# USB_Audio_DAC.net
KiCad netlist of a schematic drawn in Altium Designer
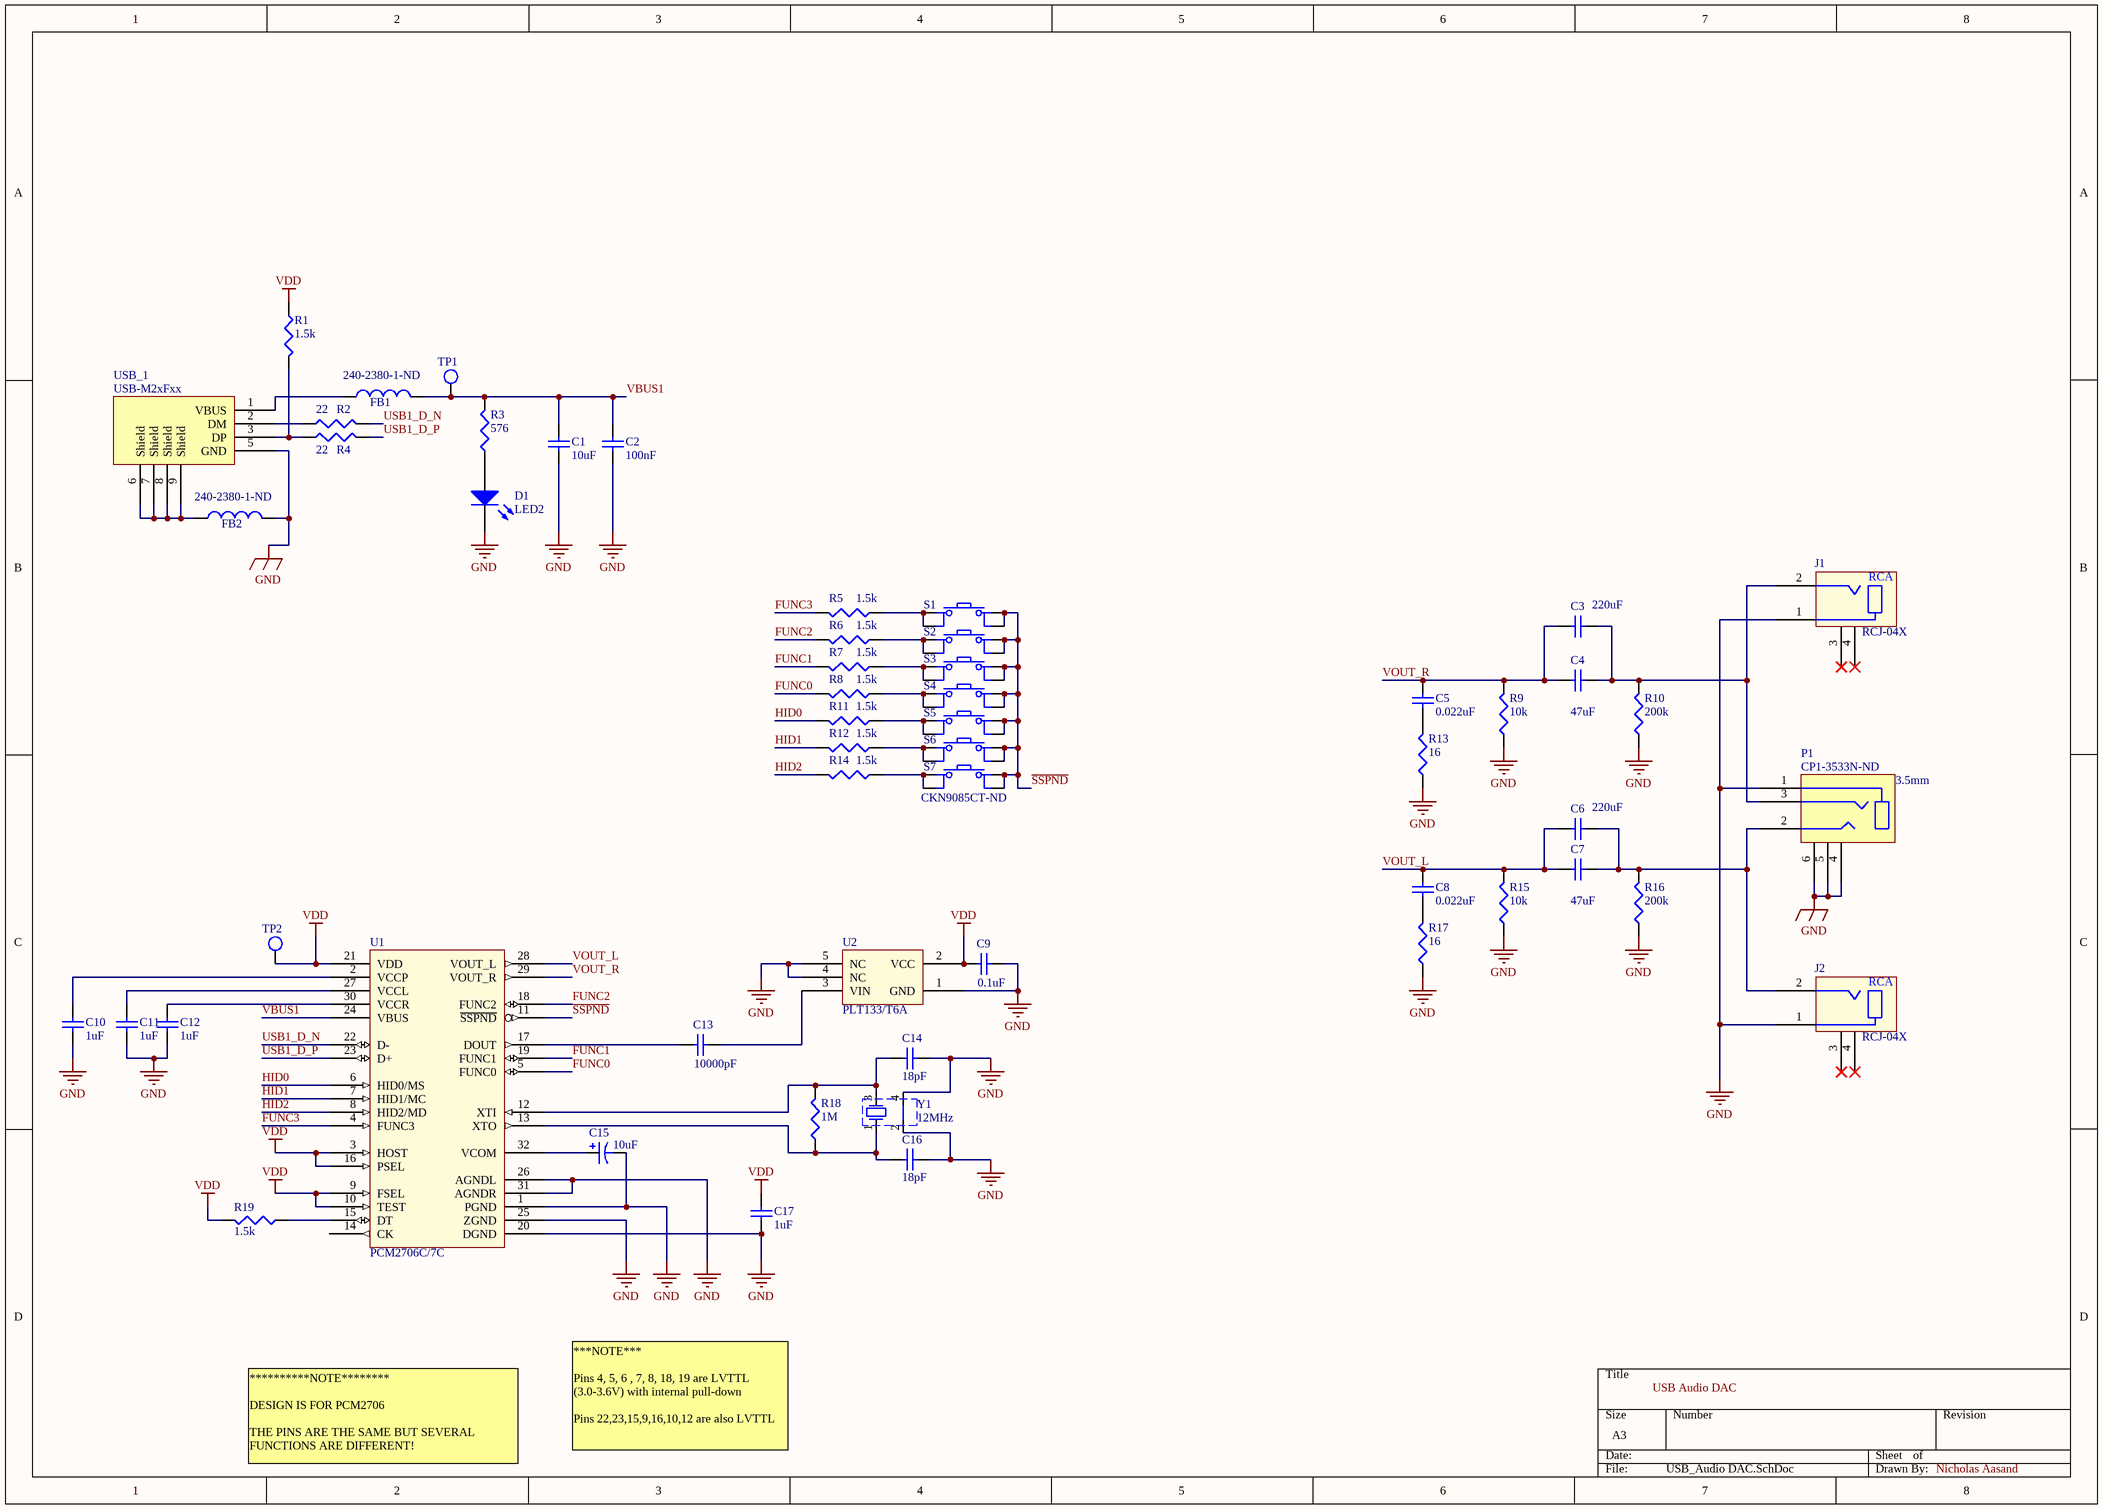
[diagram p0: USB_Audio DAC.SchDoc]

(export (version "E")
  (design (tool "Eeschema 10.0.6"))
  (components
    (comp (ref "C1")
      (value "10uF")
      (footprint "C0805")
      (description "Capacitor (Semiconductor SIM Model)")
      (fields (field (name "Comment") "0805") (field (name "PUBLISHER") "Altium Limited"))
      (libsource (lib "Miscellaneous Devices") (part "Cap Semi"))
    )
    (comp (ref "C2")
      (value "100nF")
      (footprint "C0805")
      (description "Capacitor (Semiconductor SIM Model)")
      (fields (field (name "Comment") "0805") (field (name "PUBLISHER") "Altium Limited"))
      (libsource (lib "Miscellaneous Devices") (part "Cap Semi"))
    )
    (comp (ref "C3")
      (value "220uF")
      (footprint "CAPPR5-10x12.5")
      (description "Capacitor")
      (fields (field (name "Comment") "Cap") (field (name "PUBLISHER") "Altium Limited"))
      (libsource (lib "Miscellaneous Devices") (part "Cap"))
    )
    (comp (ref "C4")
      (value "47uF")
      (footprint "CAPPR2-5x11")
      (description "Capacitor")
      (fields (field (name "Comment") "Cap") (field (name "PUBLISHER") "Altium Limited"))
      (libsource (lib "Miscellaneous Devices") (part "Cap"))
    )
    (comp (ref "C5")
      (value "0.022uF")
      (footprint "C0805")
      (description "Capacitor (Semiconductor SIM Model)")
      (fields (field (name "Comment") "0805") (field (name "PUBLISHER") "Altium Limited"))
      (libsource (lib "Miscellaneous Devices") (part "Cap Semi"))
    )
    (comp (ref "C6")
      (value "220uF")
      (footprint "CAPPR5-10x12.5")
      (description "Capacitor")
      (fields (field (name "Comment") "Cap") (field (name "PUBLISHER") "Altium Limited"))
      (libsource (lib "Miscellaneous Devices") (part "Cap"))
    )
    (comp (ref "C7")
      (value "47uF")
      (footprint "CAPPR2-5x11")
      (description "Capacitor")
      (fields (field (name "Comment") "Cap") (field (name "PUBLISHER") "Altium Limited"))
      (libsource (lib "Miscellaneous Devices") (part "Cap"))
    )
    (comp (ref "C8")
      (value "0.022uF")
      (footprint "C0805")
      (description "Capacitor (Semiconductor SIM Model)")
      (fields (field (name "Comment") "0805") (field (name "PUBLISHER") "Altium Limited"))
      (libsource (lib "Miscellaneous Devices") (part "Cap Semi"))
    )
    (comp (ref "C9")
      (value "0.1uF")
      (footprint "C0805")
      (description "Capacitor (Semiconductor SIM Model)")
      (fields (field (name "Comment") "Cap Semi") (field (name "PUBLISHER") "Altium Limited"))
      (libsource (lib "Miscellaneous Devices") (part "Cap Semi"))
    )
    (comp (ref "C10")
      (value "1uF")
      (footprint "C0805")
      (description "Capacitor (Semiconductor SIM Model)")
      (fields (field (name "Comment") "0805") (field (name "PUBLISHER") "Altium Limited"))
      (libsource (lib "Miscellaneous Devices") (part "Cap Semi"))
    )
    (comp (ref "C11")
      (value "1uF")
      (footprint "C0805")
      (description "Capacitor (Semiconductor SIM Model)")
      (fields (field (name "Comment") "0805") (field (name "PUBLISHER") "Altium Limited"))
      (libsource (lib "Miscellaneous Devices") (part "Cap Semi"))
    )
    (comp (ref "C12")
      (value "1uF")
      (footprint "C0805")
      (description "Capacitor (Semiconductor SIM Model)")
      (fields (field (name "Comment") "0805") (field (name "PUBLISHER") "Altium Limited"))
      (libsource (lib "Miscellaneous Devices") (part "Cap Semi"))
    )
    (comp (ref "C13")
      (value "10000pF")
      (footprint "C0805")
      (description "Capacitor (Semiconductor SIM Model)")
      (fields (field (name "Comment") "Cap Semi") (field (name "PUBLISHER") "Altium Limited"))
      (libsource (lib "Miscellaneous Devices") (part "Cap Semi"))
    )
    (comp (ref "C14")
      (value "18pF")
      (footprint "CAPC1608L")
      (description "Capacitor (Semiconductor SIM Model)")
      (fields (field (name "Comment") "0805") (field (name "PUBLISHER") "Altium Limited"))
      (libsource (lib "Miscellaneous Devices") (part "Cap Semi"))
    )
    (comp (ref "C15")
      (value "10uF")
      (footprint "Cap_ALUM_SMD")
      (description "Polarized Capacitor (Surface Mount)")
      (fields (field (name "Comment") "Cap Pol3") (field (name "PUBLISHER") "Altium Limited"))
      (libsource (lib "Miscellaneous Devices") (part "Cap Pol3"))
    )
    (comp (ref "C16")
      (value "18pF")
      (footprint "CAPC1608L")
      (description "Capacitor (Semiconductor SIM Model)")
      (fields (field (name "Comment") "0805") (field (name "PUBLISHER") "Altium Limited"))
      (libsource (lib "Miscellaneous Devices") (part "Cap Semi"))
    )
    (comp (ref "C17")
      (value "1uF")
      (footprint "C0805")
      (description "Capacitor (Semiconductor SIM Model)")
      (fields (field (name "Comment") "0805") (field (name "PUBLISHER") "Altium Limited"))
      (libsource (lib "Miscellaneous Devices") (part "Cap Semi"))
    )
    (comp (ref "D1")
      (value "LED2")
      (footprint "2.00mm L x 1.25mm W")
      (description "Typical RED, GREEN, YELLOW, AMBER GaAs LED")
      (fields (field (name "PUBLISHER") "Altium Limited"))
      (libsource (lib "Miscellaneous Devices") (part "LED2"))
    )
    (comp (ref "FB1")
      (value "0603")
      (footprint "INDC1608L")
      (description "Inductor")
      (fields (field (name "DIGIKEY") "240-2380-1-ND") (field (name "PUBLISHER") "Altium Limited"))
      (libsource (lib "Miscellaneous Devices") (part "Inductor"))
    )
    (comp (ref "FB2")
      (value "0603")
      (footprint "INDC1608L")
      (description "Inductor")
      (fields (field (name "DIGIKEY") "240-2380-1-ND") (field (name "PUBLISHER") "Altium Limited"))
      (libsource (lib "Miscellaneous Devices") (part "Inductor"))
    )
    (comp (ref "J1")
      (value "RCJ-04X")
      (footprint "RCJ-04X")
      (description "RCJ-04X series RCA connector")
      (libsource (lib "RCA_Audio_Jack") (part "RCJ-04X"))
    )
    (comp (ref "J2")
      (value "RCJ-04X")
      (footprint "RCJ-04X")
      (description "RCJ-04X series RCA connector")
      (libsource (lib "RCA_Audio_Jack") (part "RCJ-04X"))
    )
    (comp (ref "P1")
      (value "SJ1-3533NS")
      (footprint "SJ1-3533NS")
      (description "CUI 3.5mm Audio Jack Shielded")
      (fields (field (name "DIGIKEY") "CP1-3533N-ND"))
      (libsource (lib "Audio_Jacks") (part "SJ1-3533NS"))
    )
    (comp (ref "R1")
      (value "1.5k")
      (footprint "RESC2012L")
      (description "Resistor")
      (fields (field (name "Comment") "0805"))
      (libsource (lib "Miscellaneous Devices") (part "Res3"))
    )
    (comp (ref "R2")
      (value "22")
      (footprint "6-0805_N")
      (description "Resistor")
      (fields (field (name "Comment") "Res3") (field (name "PUBLISHER") "Altium Limited"))
      (libsource (lib "Miscellaneous Devices") (part "Res3"))
    )
    (comp (ref "R3")
      (value "576")
      (footprint "6-0805_N")
      (description "Resistor")
      (fields (field (name "Comment") "Res3") (field (name "PUBLISHER") "Altium Limited"))
      (libsource (lib "Miscellaneous Devices") (part "Res3"))
    )
    (comp (ref "R4")
      (value "22")
      (footprint "6-0805_N")
      (description "Resistor")
      (fields (field (name "Comment") "Res3") (field (name "PUBLISHER") "Altium Limited"))
      (libsource (lib "Miscellaneous Devices") (part "Res3"))
    )
    (comp (ref "R5")
      (value "1.5k")
      (footprint "RESC2012L")
      (description "Resistor")
      (fields (field (name "Comment") "0805"))
      (libsource (lib "Miscellaneous Devices") (part "Res3"))
    )
    (comp (ref "R6")
      (value "1.5k")
      (footprint "RESC2012L")
      (description "Resistor")
      (fields (field (name "Comment") "0805"))
      (libsource (lib "Miscellaneous Devices") (part "Res3"))
    )
    (comp (ref "R7")
      (value "1.5k")
      (footprint "RESC2012L")
      (description "Resistor")
      (fields (field (name "Comment") "0805"))
      (libsource (lib "Miscellaneous Devices") (part "Res3"))
    )
    (comp (ref "R8")
      (value "1.5k")
      (footprint "RESC2012L")
      (description "Resistor")
      (fields (field (name "Comment") "0805"))
      (libsource (lib "Miscellaneous Devices") (part "Res3"))
    )
    (comp (ref "R9")
      (value "10k")
      (footprint "RESC2012L")
      (description "Resistor")
      (fields (field (name "Comment") "0805"))
      (libsource (lib "Miscellaneous Devices") (part "Res3"))
    )
    (comp (ref "R10")
      (value "200k")
      (footprint "RESC2012L")
      (description "Resistor")
      (fields (field (name "Comment") "0805"))
      (libsource (lib "Miscellaneous Devices") (part "Res3"))
    )
    (comp (ref "R11")
      (value "1.5k")
      (footprint "RESC2012L")
      (description "Resistor")
      (fields (field (name "Comment") "0805"))
      (libsource (lib "Miscellaneous Devices") (part "Res3"))
    )
    (comp (ref "R12")
      (value "1.5k")
      (footprint "RESC2012L")
      (description "Resistor")
      (fields (field (name "Comment") "0805"))
      (libsource (lib "Miscellaneous Devices") (part "Res3"))
    )
    (comp (ref "R13")
      (value "16")
      (footprint "6-0805_N")
      (description "Resistor")
      (fields (field (name "Comment") "Res3") (field (name "PUBLISHER") "Altium Limited"))
      (libsource (lib "Miscellaneous Devices") (part "Res3"))
    )
    (comp (ref "R14")
      (value "1.5k")
      (footprint "RESC2012L")
      (description "Resistor")
      (fields (field (name "Comment") "0805"))
      (libsource (lib "Miscellaneous Devices") (part "Res3"))
    )
    (comp (ref "R15")
      (value "10k")
      (footprint "RESC2012L")
      (description "Resistor")
      (fields (field (name "Comment") "0805"))
      (libsource (lib "Miscellaneous Devices") (part "Res3"))
    )
    (comp (ref "R16")
      (value "200k")
      (footprint "RESC2012L")
      (description "Resistor")
      (fields (field (name "Comment") "0805"))
      (libsource (lib "Miscellaneous Devices") (part "Res3"))
    )
    (comp (ref "R17")
      (value "16")
      (footprint "6-0805_N")
      (description "Resistor")
      (fields (field (name "Comment") "Res3") (field (name "PUBLISHER") "Altium Limited"))
      (libsource (lib "Miscellaneous Devices") (part "Res3"))
    )
    (comp (ref "R18")
      (value "1M")
      (footprint "6-0805_N")
      (description "Resistor")
      (fields (field (name "Comment") "Res3") (field (name "PUBLISHER") "Altium Limited"))
      (libsource (lib "Miscellaneous Devices") (part "Res3"))
    )
    (comp (ref "R19")
      (value "1.5k")
      (footprint "RESC2012L")
      (description "Resistor")
      (fields (field (name "Comment") "0805"))
      (libsource (lib "Miscellaneous Devices") (part "Res3"))
    )
    (comp (ref "S1")
      (value "SW")
      (footprint "C&K_PTS645_SMD")
      (description "SPST Tactile switch - generic")
      (libsource (lib "Switches") (part "SPST-4"))
    )
    (comp (ref "S2")
      (value "SW")
      (footprint "C&K_PTS645_SMD")
      (description "SPST Tactile switch - generic")
      (libsource (lib "Switches") (part "SPST-4"))
    )
    (comp (ref "S3")
      (value "SW")
      (footprint "C&K_PTS645_SMD")
      (description "SPST Tactile switch - generic")
      (libsource (lib "Switches") (part "SPST-4"))
    )
    (comp (ref "S4")
      (value "SW")
      (footprint "C&K_PTS645_SMD")
      (description "SPST Tactile switch - generic")
      (libsource (lib "Switches") (part "SPST-4"))
    )
    (comp (ref "S5")
      (value "SW")
      (footprint "C&K_PTS645_SMD")
      (description "SPST Tactile switch - generic")
      (libsource (lib "Switches") (part "SPST-4"))
    )
    (comp (ref "S6")
      (value "SW")
      (footprint "C&K_PTS645_SMD")
      (description "SPST Tactile switch - generic")
      (libsource (lib "Switches") (part "SPST-4"))
    )
    (comp (ref "S7")
      (value "SW")
      (footprint "C&K_PTS645_SMD")
      (description "SPST Tactile switch - generic")
      (fields (field (name "DIGIKEY") "CKN9085CT-ND"))
      (libsource (lib "Switches") (part "SPST-4"))
    )
    (comp (ref "TP1")
      (value "Test point")
      (footprint "Test_Pad")
      (description "Test point pad")
      (libsource (lib "Connectors") (part "Test_Pad"))
    )
    (comp (ref "TP2")
      (value "Test point")
      (footprint "Test_Pad")
      (description "Test point pad")
      (libsource (lib "Connectors") (part "Test_Pad"))
    )
    (comp (ref "U1")
      (value "PCM2706C/7C")
      (footprint "TQFP80P970X970X120-32N")
      (description "Stereo Audio DAC with USB Interface, Single-Ended Headphone Out, S/PDIF Output")
      (libsource (lib "PCM2707") (part "PCM2707"))
    )
    (comp (ref "U2")
      (value "PLT133/T6A")
      (footprint "PLT133/T10W")
      (description "TRANSMITTER FBR OPT IR PHOTOLINK 660nm")
      (libsource (lib "PLT133_T6A") (part "PLT133/T6A"))
    )
    (comp (ref "USB_1")
      (value "USB-M2xFxx")
      (footprint "USB-M2xFxx")
      (description "USB Mini-B for USB-M2xFxx")
      (libsource (lib "USB-M2xFxx") (part "USB-M2xFxx"))
    )
    (comp (ref "Y1")
      (value "12MHz")
      (footprint "TXC-7M")
      (description "Crystal Oscillator - 4 Pin")
      (libsource (lib "XTALS") (part "XTAL-4"))
    )
  )
  (nets
    (net (code "1") (name "/FUNC0") (class "Default")
      (node (ref "R8") (pin "2") (pinfunction "2_2") (pintype "passive"))
      (node (ref "U1") (pin "5") (pinfunction "FUNC0_5") (pintype "bidirectional"))
    )
    (net (code "2") (name "/FUNC1") (class "Default")
      (node (ref "R7") (pin "2") (pinfunction "2_2") (pintype "passive"))
      (node (ref "U1") (pin "19") (pinfunction "FUNC1_19") (pintype "bidirectional"))
    )
    (net (code "3") (name "/FUNC2") (class "Default")
      (node (ref "R6") (pin "2") (pinfunction "2_2") (pintype "passive"))
      (node (ref "U1") (pin "18") (pinfunction "FUNC2_18") (pintype "bidirectional"))
    )
    (net (code "4") (name "/FUNC3") (class "Default")
      (node (ref "R5") (pin "2") (pinfunction "2_2") (pintype "passive"))
      (node (ref "U1") (pin "4") (pinfunction "FUNC3_4") (pintype "input"))
    )
    (net (code "5") (name "/HID0") (class "Default")
      (node (ref "R11") (pin "2") (pinfunction "2_2") (pintype "passive"))
      (node (ref "U1") (pin "6") (pinfunction "HID0/MS_6") (pintype "input"))
    )
    (net (code "6") (name "/HID1") (class "Default")
      (node (ref "R12") (pin "2") (pinfunction "2_2") (pintype "passive"))
      (node (ref "U1") (pin "7") (pinfunction "HID1/MC_7") (pintype "input"))
    )
    (net (code "7") (name "/HID2") (class "Default")
      (node (ref "R14") (pin "2") (pinfunction "2_2") (pintype "passive"))
      (node (ref "U1") (pin "8") (pinfunction "HID2/MD_8") (pintype "input"))
    )
    (net (code "8") (name "/USB1_D_N") (class "Default")
      (node (ref "R2") (pin "2") (pinfunction "2_2") (pintype "passive"))
      (node (ref "U1") (pin "22") (pinfunction "D-_22") (pintype "bidirectional"))
    )
    (net (code "9") (name "/USB1_D_P") (class "Default")
      (node (ref "R4") (pin "2") (pinfunction "2_2") (pintype "passive"))
      (node (ref "U1") (pin "23") (pinfunction "D+_23") (pintype "bidirectional"))
    )
    (net (code "10") (name "/VBUS1") (class "Default")
      (node (ref "C1") (pin "1") (pinfunction "1_1") (pintype "passive"))
      (node (ref "C2") (pin "1") (pinfunction "1_1") (pintype "passive"))
      (node (ref "FB1") (pin "2") (pinfunction "2_2") (pintype "passive"))
      (node (ref "R3") (pin "2") (pinfunction "2_2") (pintype "passive"))
      (node (ref "TP1") (pin "1") (pinfunction "1_1") (pintype "passive"))
      (node (ref "U1") (pin "24") (pinfunction "VBUS_24") (pintype "power_in"))
    )
    (net (code "11") (name "/VOUT_L") (class "Default")
      (node (ref "C6") (pin "1") (pinfunction "1_1") (pintype "passive"))
      (node (ref "C7") (pin "1") (pinfunction "1_1") (pintype "passive"))
      (node (ref "C8") (pin "1") (pinfunction "1_1") (pintype "passive"))
      (node (ref "R15") (pin "2") (pinfunction "2_2") (pintype "passive"))
      (node (ref "U1") (pin "28") (pinfunction "VOUT_L_28") (pintype "output"))
    )
    (net (code "12") (name "/VOUT_R") (class "Default")
      (node (ref "C3") (pin "1") (pinfunction "1_1") (pintype "passive"))
      (node (ref "C4") (pin "1") (pinfunction "1_1") (pintype "passive"))
      (node (ref "C5") (pin "1") (pinfunction "1_1") (pintype "passive"))
      (node (ref "R9") (pin "2") (pinfunction "2_2") (pintype "passive"))
      (node (ref "U1") (pin "29") (pinfunction "VOUT_R_29") (pintype "output"))
    )
    (net (code "13") (name "/~{SSPND}") (class "Default")
      (node (ref "S1") (pin "2") (pinfunction "2_2") (pintype "passive"))
      (node (ref "S1") (pin "4") (pinfunction "4_4") (pintype "passive"))
      (node (ref "S2") (pin "2") (pinfunction "2_2") (pintype "passive"))
      (node (ref "S2") (pin "4") (pinfunction "4_4") (pintype "passive"))
      (node (ref "S3") (pin "2") (pinfunction "2_2") (pintype "passive"))
      (node (ref "S3") (pin "4") (pinfunction "4_4") (pintype "passive"))
      (node (ref "S4") (pin "2") (pinfunction "2_2") (pintype "passive"))
      (node (ref "S4") (pin "4") (pinfunction "4_4") (pintype "passive"))
      (node (ref "S5") (pin "2") (pinfunction "2_2") (pintype "passive"))
      (node (ref "S5") (pin "4") (pinfunction "4_4") (pintype "passive"))
      (node (ref "S6") (pin "2") (pinfunction "2_2") (pintype "passive"))
      (node (ref "S6") (pin "4") (pinfunction "4_4") (pintype "passive"))
      (node (ref "S7") (pin "2") (pinfunction "2_2") (pintype "passive"))
      (node (ref "S7") (pin "4") (pinfunction "4_4") (pintype "passive"))
      (node (ref "U1") (pin "11") (pinfunction "~{SSPND}_11") (pintype "output"))
    )
    (net (code "14") (name "GND") (class "Default")
      (node (ref "C1") (pin "2") (pinfunction "2_2") (pintype "passive"))
      (node (ref "C10") (pin "2") (pinfunction "2_2") (pintype "passive"))
      (node (ref "C11") (pin "2") (pinfunction "2_2") (pintype "passive"))
      (node (ref "C12") (pin "2") (pinfunction "2_2") (pintype "passive"))
      (node (ref "C14") (pin "1") (pinfunction "1_1") (pintype "passive"))
      (node (ref "C15") (pin "2") (pinfunction "2_2") (pintype "passive"))
      (node (ref "C16") (pin "1") (pinfunction "1_1") (pintype "passive"))
      (node (ref "C17") (pin "2") (pinfunction "2_2") (pintype "passive"))
      (node (ref "C2") (pin "2") (pinfunction "2_2") (pintype "passive"))
      (node (ref "C9") (pin "2") (pinfunction "2_2") (pintype "passive"))
      (node (ref "D1") (pin "2") (pinfunction "K_2") (pintype "passive"))
      (node (ref "FB2") (pin "2") (pinfunction "2_2") (pintype "passive"))
      (node (ref "J1") (pin "1") (pinfunction "GND_1") (pintype "power_in"))
      (node (ref "J2") (pin "1") (pinfunction "GND_1") (pintype "power_in"))
      (node (ref "P1") (pin "1") (pinfunction "Sleeve_1") (pintype "passive"))
      (node (ref "P1") (pin "4") (pinfunction "Shield_4") (pintype "passive"))
      (node (ref "P1") (pin "5") (pinfunction "Shield_5") (pintype "passive"))
      (node (ref "P1") (pin "6") (pinfunction "Shield_6") (pintype "passive"))
      (node (ref "R10") (pin "1") (pinfunction "1_1") (pintype "passive"))
      (node (ref "R13") (pin "1") (pinfunction "1_1") (pintype "passive"))
      (node (ref "R15") (pin "1") (pinfunction "1_1") (pintype "passive"))
      (node (ref "R16") (pin "1") (pinfunction "1_1") (pintype "passive"))
      (node (ref "R17") (pin "1") (pinfunction "1_1") (pintype "passive"))
      (node (ref "R9") (pin "1") (pinfunction "1_1") (pintype "passive"))
      (node (ref "U1") (pin "1") (pinfunction "PGND_1") (pintype "power_in"))
      (node (ref "U1") (pin "20") (pinfunction "DGND_20") (pintype "power_in"))
      (node (ref "U1") (pin "25") (pinfunction "ZGND_25") (pintype "power_in"))
      (node (ref "U1") (pin "26") (pinfunction "AGNDL_26") (pintype "power_in"))
      (node (ref "U1") (pin "31") (pinfunction "AGNDR_31") (pintype "power_in"))
      (node (ref "U2") (pin "1") (pinfunction "GND_1") (pintype "passive"))
      (node (ref "U2") (pin "4") (pinfunction "NC_4") (pintype "passive"))
      (node (ref "U2") (pin "5") (pinfunction "NC_5") (pintype "passive"))
      (node (ref "USB_1") (pin "5") (pinfunction "GND_5") (pintype "passive"))
      (node (ref "Y1") (pin "2") (pinfunction "2_2") (pintype "passive"))
      (node (ref "Y1") (pin "4") (pinfunction "4_4") (pintype "passive"))
    )
    (net (code "15") (name "Net-(C5-Pad2)") (class "Default")
      (node (ref "C5") (pin "2") (pinfunction "2_2") (pintype "passive"))
      (node (ref "R13") (pin "2") (pinfunction "2_2") (pintype "passive"))
    )
    (net (code "16") (name "Net-(C8-Pad2)") (class "Default")
      (node (ref "C8") (pin "2") (pinfunction "2_2") (pintype "passive"))
      (node (ref "R17") (pin "2") (pinfunction "2_2") (pintype "passive"))
    )
    (net (code "17") (name "Net-(D1-A)") (class "Default")
      (node (ref "D1") (pin "1") (pinfunction "A_1") (pintype "passive"))
      (node (ref "R3") (pin "1") (pinfunction "1_1") (pintype "passive"))
    )
    (net (code "18") (name "Net-(FB2-Pad1)") (class "Default")
      (node (ref "FB2") (pin "1") (pinfunction "1_1") (pintype "passive"))
      (node (ref "USB_1") (pin "6") (pinfunction "Shield_6") (pintype "passive"))
      (node (ref "USB_1") (pin "7") (pinfunction "Shield_7") (pintype "passive"))
      (node (ref "USB_1") (pin "8") (pinfunction "Shield_8") (pintype "passive"))
      (node (ref "USB_1") (pin "9") (pinfunction "Shield_9") (pintype "passive"))
    )
    (net (code "19") (name "Net-(J1-Vin)") (class "Default")
      (node (ref "C3") (pin "2") (pinfunction "2_2") (pintype "passive"))
      (node (ref "C4") (pin "2") (pinfunction "2_2") (pintype "passive"))
      (node (ref "J1") (pin "2") (pinfunction "Vin_2") (pintype "passive"))
      (node (ref "P1") (pin "3") (pinfunction "Ring_3") (pintype "passive"))
      (node (ref "R10") (pin "2") (pinfunction "2_2") (pintype "passive"))
    )
    (net (code "20") (name "Net-(J2-Vin)") (class "Default")
      (node (ref "C6") (pin "2") (pinfunction "2_2") (pintype "passive"))
      (node (ref "C7") (pin "2") (pinfunction "2_2") (pintype "passive"))
      (node (ref "J2") (pin "2") (pinfunction "Vin_2") (pintype "passive"))
      (node (ref "P1") (pin "2") (pinfunction "Tip_2") (pintype "passive"))
      (node (ref "R16") (pin "2") (pinfunction "2_2") (pintype "passive"))
    )
    (net (code "21") (name "Net-(R5-Pad1)") (class "Default")
      (node (ref "R5") (pin "1") (pinfunction "1_1") (pintype "passive"))
      (node (ref "S1") (pin "1") (pinfunction "1_1") (pintype "passive"))
      (node (ref "S1") (pin "3") (pinfunction "3_3") (pintype "passive"))
    )
    (net (code "22") (name "Net-(R6-Pad1)") (class "Default")
      (node (ref "R6") (pin "1") (pinfunction "1_1") (pintype "passive"))
      (node (ref "S2") (pin "1") (pinfunction "1_1") (pintype "passive"))
      (node (ref "S2") (pin "3") (pinfunction "3_3") (pintype "passive"))
    )
    (net (code "23") (name "Net-(R7-Pad1)") (class "Default")
      (node (ref "R7") (pin "1") (pinfunction "1_1") (pintype "passive"))
      (node (ref "S3") (pin "1") (pinfunction "1_1") (pintype "passive"))
      (node (ref "S3") (pin "3") (pinfunction "3_3") (pintype "passive"))
    )
    (net (code "24") (name "Net-(R8-Pad1)") (class "Default")
      (node (ref "R8") (pin "1") (pinfunction "1_1") (pintype "passive"))
      (node (ref "S4") (pin "1") (pinfunction "1_1") (pintype "passive"))
      (node (ref "S4") (pin "3") (pinfunction "3_3") (pintype "passive"))
    )
    (net (code "25") (name "Net-(R11-Pad1)") (class "Default")
      (node (ref "R11") (pin "1") (pinfunction "1_1") (pintype "passive"))
      (node (ref "S5") (pin "1") (pinfunction "1_1") (pintype "passive"))
      (node (ref "S5") (pin "3") (pinfunction "3_3") (pintype "passive"))
    )
    (net (code "26") (name "Net-(R12-Pad1)") (class "Default")
      (node (ref "R12") (pin "1") (pinfunction "1_1") (pintype "passive"))
      (node (ref "S6") (pin "1") (pinfunction "1_1") (pintype "passive"))
      (node (ref "S6") (pin "3") (pinfunction "3_3") (pintype "passive"))
    )
    (net (code "27") (name "Net-(R14-Pad1)") (class "Default")
      (node (ref "R14") (pin "1") (pinfunction "1_1") (pintype "passive"))
      (node (ref "S7") (pin "1") (pinfunction "1_1") (pintype "passive"))
      (node (ref "S7") (pin "3") (pinfunction "3_3") (pintype "passive"))
    )
    (net (code "28") (name "Net-(U1-DOUT)") (class "Default")
      (node (ref "C13") (pin "1") (pinfunction "1_1") (pintype "passive"))
      (node (ref "U1") (pin "17") (pinfunction "DOUT_17") (pintype "output"))
    )
    (net (code "29") (name "Net-(U1-DT)") (class "Default")
      (node (ref "R19") (pin "1") (pinfunction "1_1") (pintype "passive"))
      (node (ref "U1") (pin "15") (pinfunction "DT_15") (pintype "bidirectional"))
    )
    (net (code "30") (name "Net-(U1-VCCL)") (class "Default")
      (node (ref "C11") (pin "1") (pinfunction "1_1") (pintype "passive"))
      (node (ref "U1") (pin "27") (pinfunction "VCCL_27") (pintype "power_in"))
    )
    (net (code "31") (name "Net-(U1-VCCP)") (class "Default")
      (node (ref "C10") (pin "1") (pinfunction "1_1") (pintype "passive"))
      (node (ref "U1") (pin "2") (pinfunction "VCCP_2") (pintype "power_in"))
    )
    (net (code "32") (name "Net-(U1-VCCR)") (class "Default")
      (node (ref "C12") (pin "1") (pinfunction "1_1") (pintype "passive"))
      (node (ref "U1") (pin "30") (pinfunction "VCCR_30") (pintype "power_in"))
    )
    (net (code "33") (name "Net-(U1-VCOM)") (class "Default")
      (node (ref "C15") (pin "1") (pinfunction "1_1") (pintype "passive"))
      (node (ref "U1") (pin "32") (pinfunction "VCOM_32") (pintype "power_in"))
    )
    (net (code "34") (name "Net-(U1-XTI)") (class "Default")
      (node (ref "C14") (pin "2") (pinfunction "2_2") (pintype "passive"))
      (node (ref "R18") (pin "2") (pinfunction "2_2") (pintype "passive"))
      (node (ref "U1") (pin "12") (pinfunction "XTI_12") (pintype "input"))
      (node (ref "Y1") (pin "3") (pinfunction "3_3") (pintype "passive"))
    )
    (net (code "35") (name "Net-(U1-XTO)") (class "Default")
      (node (ref "C16") (pin "2") (pinfunction "2_2") (pintype "passive"))
      (node (ref "R18") (pin "1") (pinfunction "1_1") (pintype "passive"))
      (node (ref "U1") (pin "13") (pinfunction "XTO_13") (pintype "output"))
      (node (ref "Y1") (pin "1") (pinfunction "1_1") (pintype "passive"))
    )
    (net (code "36") (name "Net-(U2-VIN)") (class "Default")
      (node (ref "C13") (pin "2") (pinfunction "2_2") (pintype "passive"))
      (node (ref "U2") (pin "3") (pinfunction "VIN_3") (pintype "passive"))
    )
    (net (code "37") (name "Net-(USB_1-DM)") (class "Default")
      (node (ref "R2") (pin "1") (pinfunction "1_1") (pintype "passive"))
      (node (ref "USB_1") (pin "2") (pinfunction "DM_2") (pintype "passive"))
    )
    (net (code "38") (name "Net-(USB_1-DP)") (class "Default")
      (node (ref "R1") (pin "2") (pinfunction "2_2") (pintype "passive"))
      (node (ref "R4") (pin "1") (pinfunction "1_1") (pintype "passive"))
      (node (ref "USB_1") (pin "3") (pinfunction "DP_3") (pintype "passive"))
    )
    (net (code "39") (name "Net-(USB_1-VBUS)") (class "Default")
      (node (ref "FB1") (pin "1") (pinfunction "1_1") (pintype "passive"))
      (node (ref "USB_1") (pin "1") (pinfunction "VBUS_1") (pintype "passive"))
    )
    (net (code "40") (name "VDD") (class "Default")
      (node (ref "C17") (pin "1") (pinfunction "1_1") (pintype "passive"))
      (node (ref "C9") (pin "1") (pinfunction "1_1") (pintype "passive"))
      (node (ref "R1") (pin "1") (pinfunction "1_1") (pintype "passive"))
      (node (ref "R19") (pin "2") (pinfunction "2_2") (pintype "passive"))
      (node (ref "TP2") (pin "1") (pinfunction "1_1") (pintype "passive"))
      (node (ref "U1") (pin "10") (pinfunction "TEST_10") (pintype "input"))
      (node (ref "U1") (pin "16") (pinfunction "PSEL_16") (pintype "input"))
      (node (ref "U1") (pin "21") (pinfunction "VDD_21") (pintype "power_in"))
      (node (ref "U1") (pin "3") (pinfunction "HOST_3") (pintype "input"))
      (node (ref "U1") (pin "9") (pinfunction "FSEL_9") (pintype "input"))
      (node (ref "U2") (pin "2") (pinfunction "VCC_2") (pintype "passive"))
    )
    (net (code "41") (name "unconnected-(J1-NC-Pad3)") (class "Default")
      (node (ref "J1") (pin "3") (pinfunction "NC_3") (pintype "passive+no_connect"))
    )
    (net (code "42") (name "unconnected-(J1-NC-Pad4)") (class "Default")
      (node (ref "J1") (pin "4") (pinfunction "NC_4") (pintype "passive+no_connect"))
    )
    (net (code "43") (name "unconnected-(J2-NC-Pad3)") (class "Default")
      (node (ref "J2") (pin "3") (pinfunction "NC_3") (pintype "passive+no_connect"))
    )
    (net (code "44") (name "unconnected-(J2-NC-Pad4)") (class "Default")
      (node (ref "J2") (pin "4") (pinfunction "NC_4") (pintype "passive+no_connect"))
    )
    (net (code "45") (name "unconnected-(U1-CK-Pad14)") (class "Default")
      (node (ref "U1") (pin "14") (pinfunction "CK_14") (pintype "output"))
    )
    (net (code "46") (name "unconnected-(USB_1-NC-Pad4)") (class "Default")
      (node (ref "USB_1") (pin "4") (pinfunction "NC_4") (pintype "passive"))
    )
  )
)
